# ProportionalSolenoid.net
KiCad netlist of a schematic drawn in Altium Designer
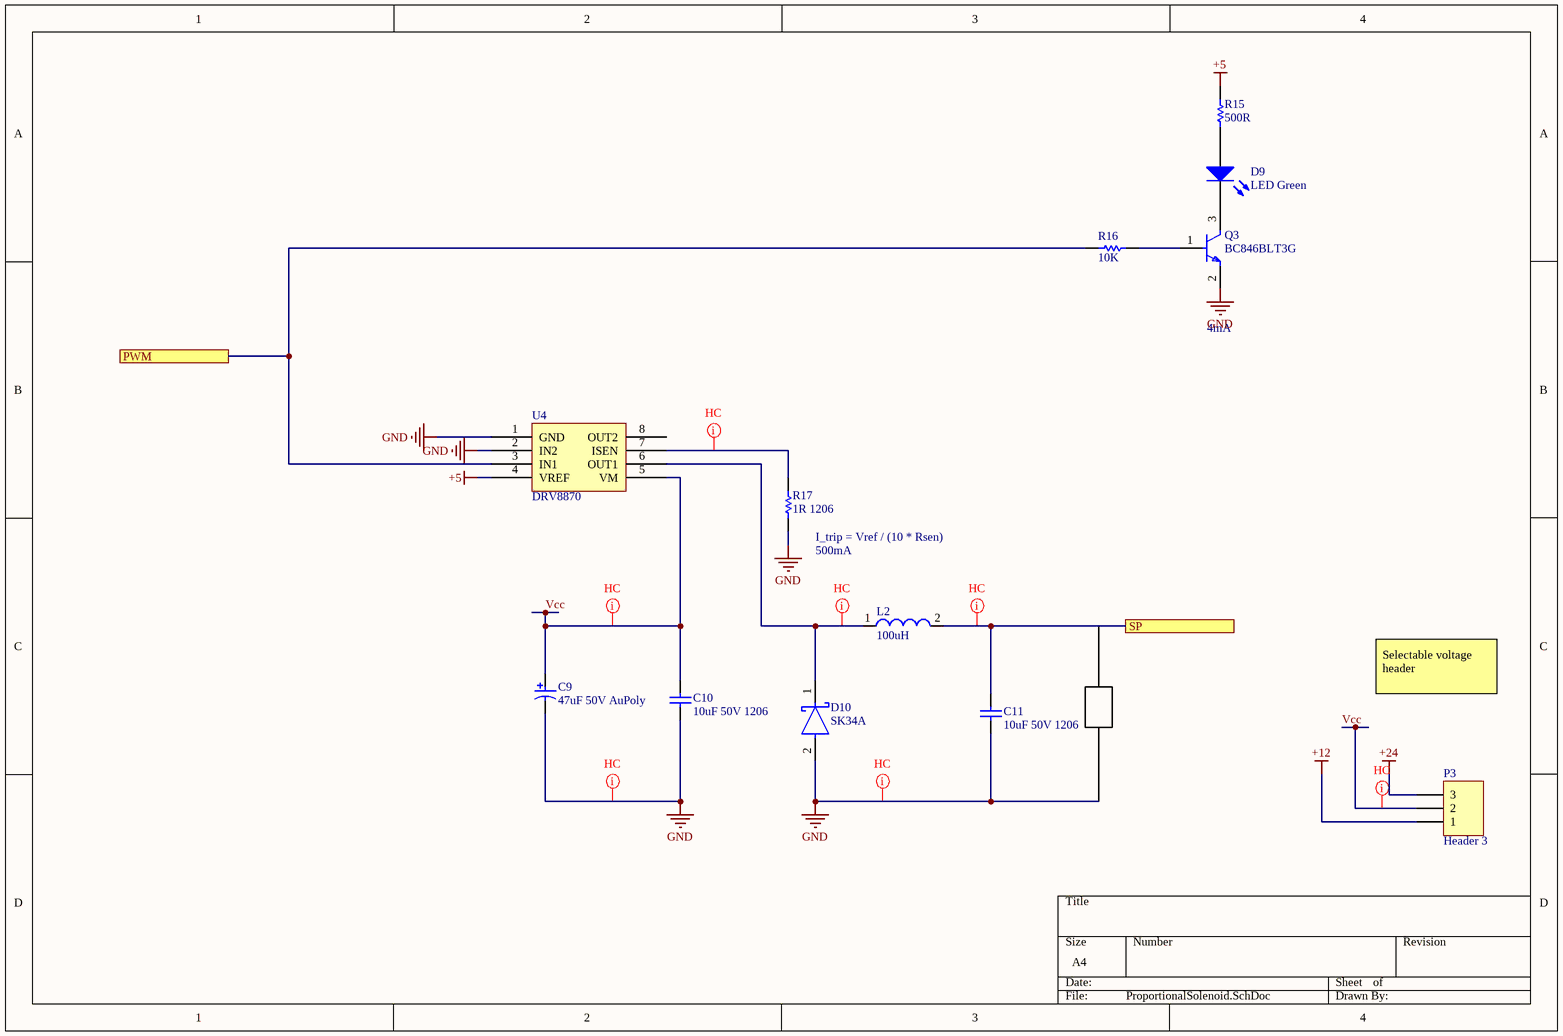
[diagram p0: ProportionalSolenoid.SchDoc]

(export (version "E")
  (design (tool "Eeschema 10.0.6"))
  (components
    (comp (ref "C9")
      (value "47uF 50V AuPoly")
      (footprint "EEH-ZA1H220P")
      (fields (field (name "VOLTAGE") "25VDC") (field (name "MANUFACTURER") "AVX"))
      (libsource (lib "Schlib1") (part "C-Poly"))
    )
    (comp (ref "C10")
      (value "10uF 50V 1206")
      (footprint "CAPC1206(3216)190_N")
      (description "CAP 10uF 50V ±20% 1206 (3216 Metric) Thickness 1.9mm SMD")
      (fields (field (name "TOLERANCE") "Â±20%"))
      (libsource (lib "Altium Content Vault") (part "CAP"))
    )
    (comp (ref "C11")
      (value "10uF 50V 1206")
      (footprint "CAPC1206(3216)190_N")
      (description "CAP 10uF 50V ±20% 1206 (3216 Metric) Thickness 1.9mm SMD")
      (fields (field (name "TOLERANCE") "Â±20%"))
      (libsource (lib "Altium Content Vault") (part "CAP"))
    )
    (comp (ref "D9")
      (value "LED Green")
      (footprint "0603_A")
      (description "SMD mono-color Chip LED, WL-SMCW, Green")
      (fields (field (name "PARTNUMBER") "150060GS75000") (field (name "MANUFACTURER") "Wuerth Elektronik"))
      (libsource (lib "Altium Content Vault") (part "WE-LED_K1A2-2"))
    )
    (comp (ref "D10")
      (value "SK34A")
      (footprint "FP-DO-214AC-MFG")
      (description "DIODE SCHOTTKY 5A 30V SMA")
      (libsource (lib "Altium Content Vault") (part "1d6ec82d83fb6aee721767c19dac4b9"))
    )
    (comp (ref "L2")
      (value "100uH")
      (footprint "L0404")
      (fields (field (name "MANUFACTURER") "Wuerth Elektronik") (field (name "PARTNUMBER") "74479763215"))
      (libsource (lib "Schlib1") (part "Inductor0404"))
    )
    (comp (ref "P3")
      (value "Header 3")
      (footprint "HDR1X3")
      (description "Header, 3-Pin")
      (fields (field (name "PUBLISHER") "Altium Limited"))
      (libsource (lib "Miscellaneous Connectors") (part "Header 3"))
    )
    (comp (ref "Q3")
      (value "BC846BLT3G")
      (footprint "FP-318-08-IPC_C")
      (description "TRANS NPN 65V 0.1A SOT-23")
      (libsource (lib "Altium Content Vault") (part "2a1388f82443b098dcd57d24ac7632d"))
    )
    (comp (ref "R15")
      (value "500R")
      (footprint "RESC0603(1608)_L")
      (description "510R 0.1W 5% 0603 (1608 Metric)  SMD")
      (fields (field (name "POWER") "0.1 W") (field (name "TOLERANCE") "5 %"))
      (libsource (lib "Altium Content Vault") (part "RES"))
    )
    (comp (ref "R16")
      (value "10K")
      (footprint "RESC0603(1608)_N")
      (description "10K 0.1W 1% 0603 (1608 Metric)  SMD")
      (fields (field (name "POWER") "0.1 W") (field (name "TOLERANCE") "1 %"))
      (libsource (lib "Altium Content Vault") (part "RES"))
    )
    (comp (ref "R17")
      (value "1R 1206")
      (footprint "RESC1206(3216)_N")
      (description "1R2 0.25W 5% 1206 (3216 Metric)  SMD")
      (fields (field (name "POWER") "0.25 W") (field (name "TOLERANCE") "5 %"))
      (libsource (lib "Altium Content Vault") (part "RES"))
    )
    (comp (ref "U4")
      (value "DRV8870")
      (footprint "SOIC127P600X170_HS-9N")
      (libsource (lib "Schlib1") (part "DRV8870"))
    )
  )
  (nets
    (net (code "1") (name "+5") (class "Default")
      (node (ref "R15") (pin "2") (pinfunction "2_2") (pintype "passive"))
      (node (ref "U4") (pin "4") (pinfunction "VREF_4") (pintype "passive"))
    )
    (net (code "2") (name "+12") (class "Default")
      (node (ref "P3") (pin "1") (pinfunction "1_1") (pintype "passive"))
    )
    (net (code "3") (name "+24") (class "Default")
      (node (ref "P3") (pin "3") (pinfunction "3_3") (pintype "passive"))
    )
    (net (code "4") (name "/PWM") (class "Default")
      (node (ref "R16") (pin "1") (pinfunction "1_1") (pintype "passive"))
      (node (ref "U4") (pin "3") (pinfunction "IN1_3") (pintype "passive"))
    )
    (net (code "5") (name "/SP") (class "Default")
      (node (ref "C11") (pin "2") (pinfunction "2_2") (pintype "passive"))
      (node (ref "L2") (pin "2") (pinfunction "2_2") (pintype "passive"))
    )
    (net (code "6") (name "/Vcc") (class "Default")
      (node (ref "C10") (pin "2") (pinfunction "2_2") (pintype "passive"))
      (node (ref "C9") (pin "1") (pinfunction "1_1") (pintype "passive"))
      (node (ref "P3") (pin "2") (pinfunction "2_2") (pintype "passive"))
      (node (ref "U4") (pin "5") (pinfunction "VM_5") (pintype "passive"))
    )
    (net (code "7") (name "GND") (class "Default")
      (node (ref "C10") (pin "1") (pinfunction "1_1") (pintype "passive"))
      (node (ref "C11") (pin "1") (pinfunction "1_1") (pintype "passive"))
      (node (ref "C9") (pin "2") (pinfunction "2_2") (pintype "passive"))
      (node (ref "D10") (pin "2") (pinfunction "A_2") (pintype "passive"))
      (node (ref "Q3") (pin "2") (pinfunction "E_2") (pintype "passive"))
      (node (ref "R17") (pin "1") (pinfunction "1_1") (pintype "passive"))
      (node (ref "U4") (pin "1") (pinfunction "GND_1") (pintype "passive"))
      (node (ref "U4") (pin "2") (pinfunction "IN2_2") (pintype "passive"))
    )
    (net (code "8") (name "Net-(D9-A)") (class "Default")
      (node (ref "D9") (pin "2") (pinfunction "A_2") (pintype "passive"))
      (node (ref "R15") (pin "1") (pinfunction "1_1") (pintype "passive"))
    )
    (net (code "9") (name "Net-(D9-K)") (class "Default")
      (node (ref "D9") (pin "1") (pinfunction "K_1") (pintype "passive"))
      (node (ref "Q3") (pin "3") (pinfunction "C_3") (pintype "passive"))
    )
    (net (code "10") (name "Net-(D10-C)") (class "Default")
      (node (ref "D10") (pin "1") (pinfunction "C_1") (pintype "passive"))
      (node (ref "L2") (pin "1") (pinfunction "1_1") (pintype "passive"))
      (node (ref "U4") (pin "6") (pinfunction "OUT1_6") (pintype "passive"))
    )
    (net (code "11") (name "Net-(Q3-B)") (class "Default")
      (node (ref "Q3") (pin "1") (pinfunction "B_1") (pintype "passive"))
      (node (ref "R16") (pin "2") (pinfunction "2_2") (pintype "passive"))
    )
    (net (code "12") (name "Net-(U4-ISEN)") (class "Default")
      (node (ref "R17") (pin "2") (pinfunction "2_2") (pintype "passive"))
      (node (ref "U4") (pin "7") (pinfunction "ISEN_7") (pintype "passive"))
    )
    (net (code "13") (name "unconnected-(U4-OUT2-Pad8)") (class "Default")
      (node (ref "U4") (pin "8") (pinfunction "OUT2_8") (pintype "passive"))
    )
  )
)
